# DDR3.net
KiCad netlist of a schematic drawn in Altium Designer
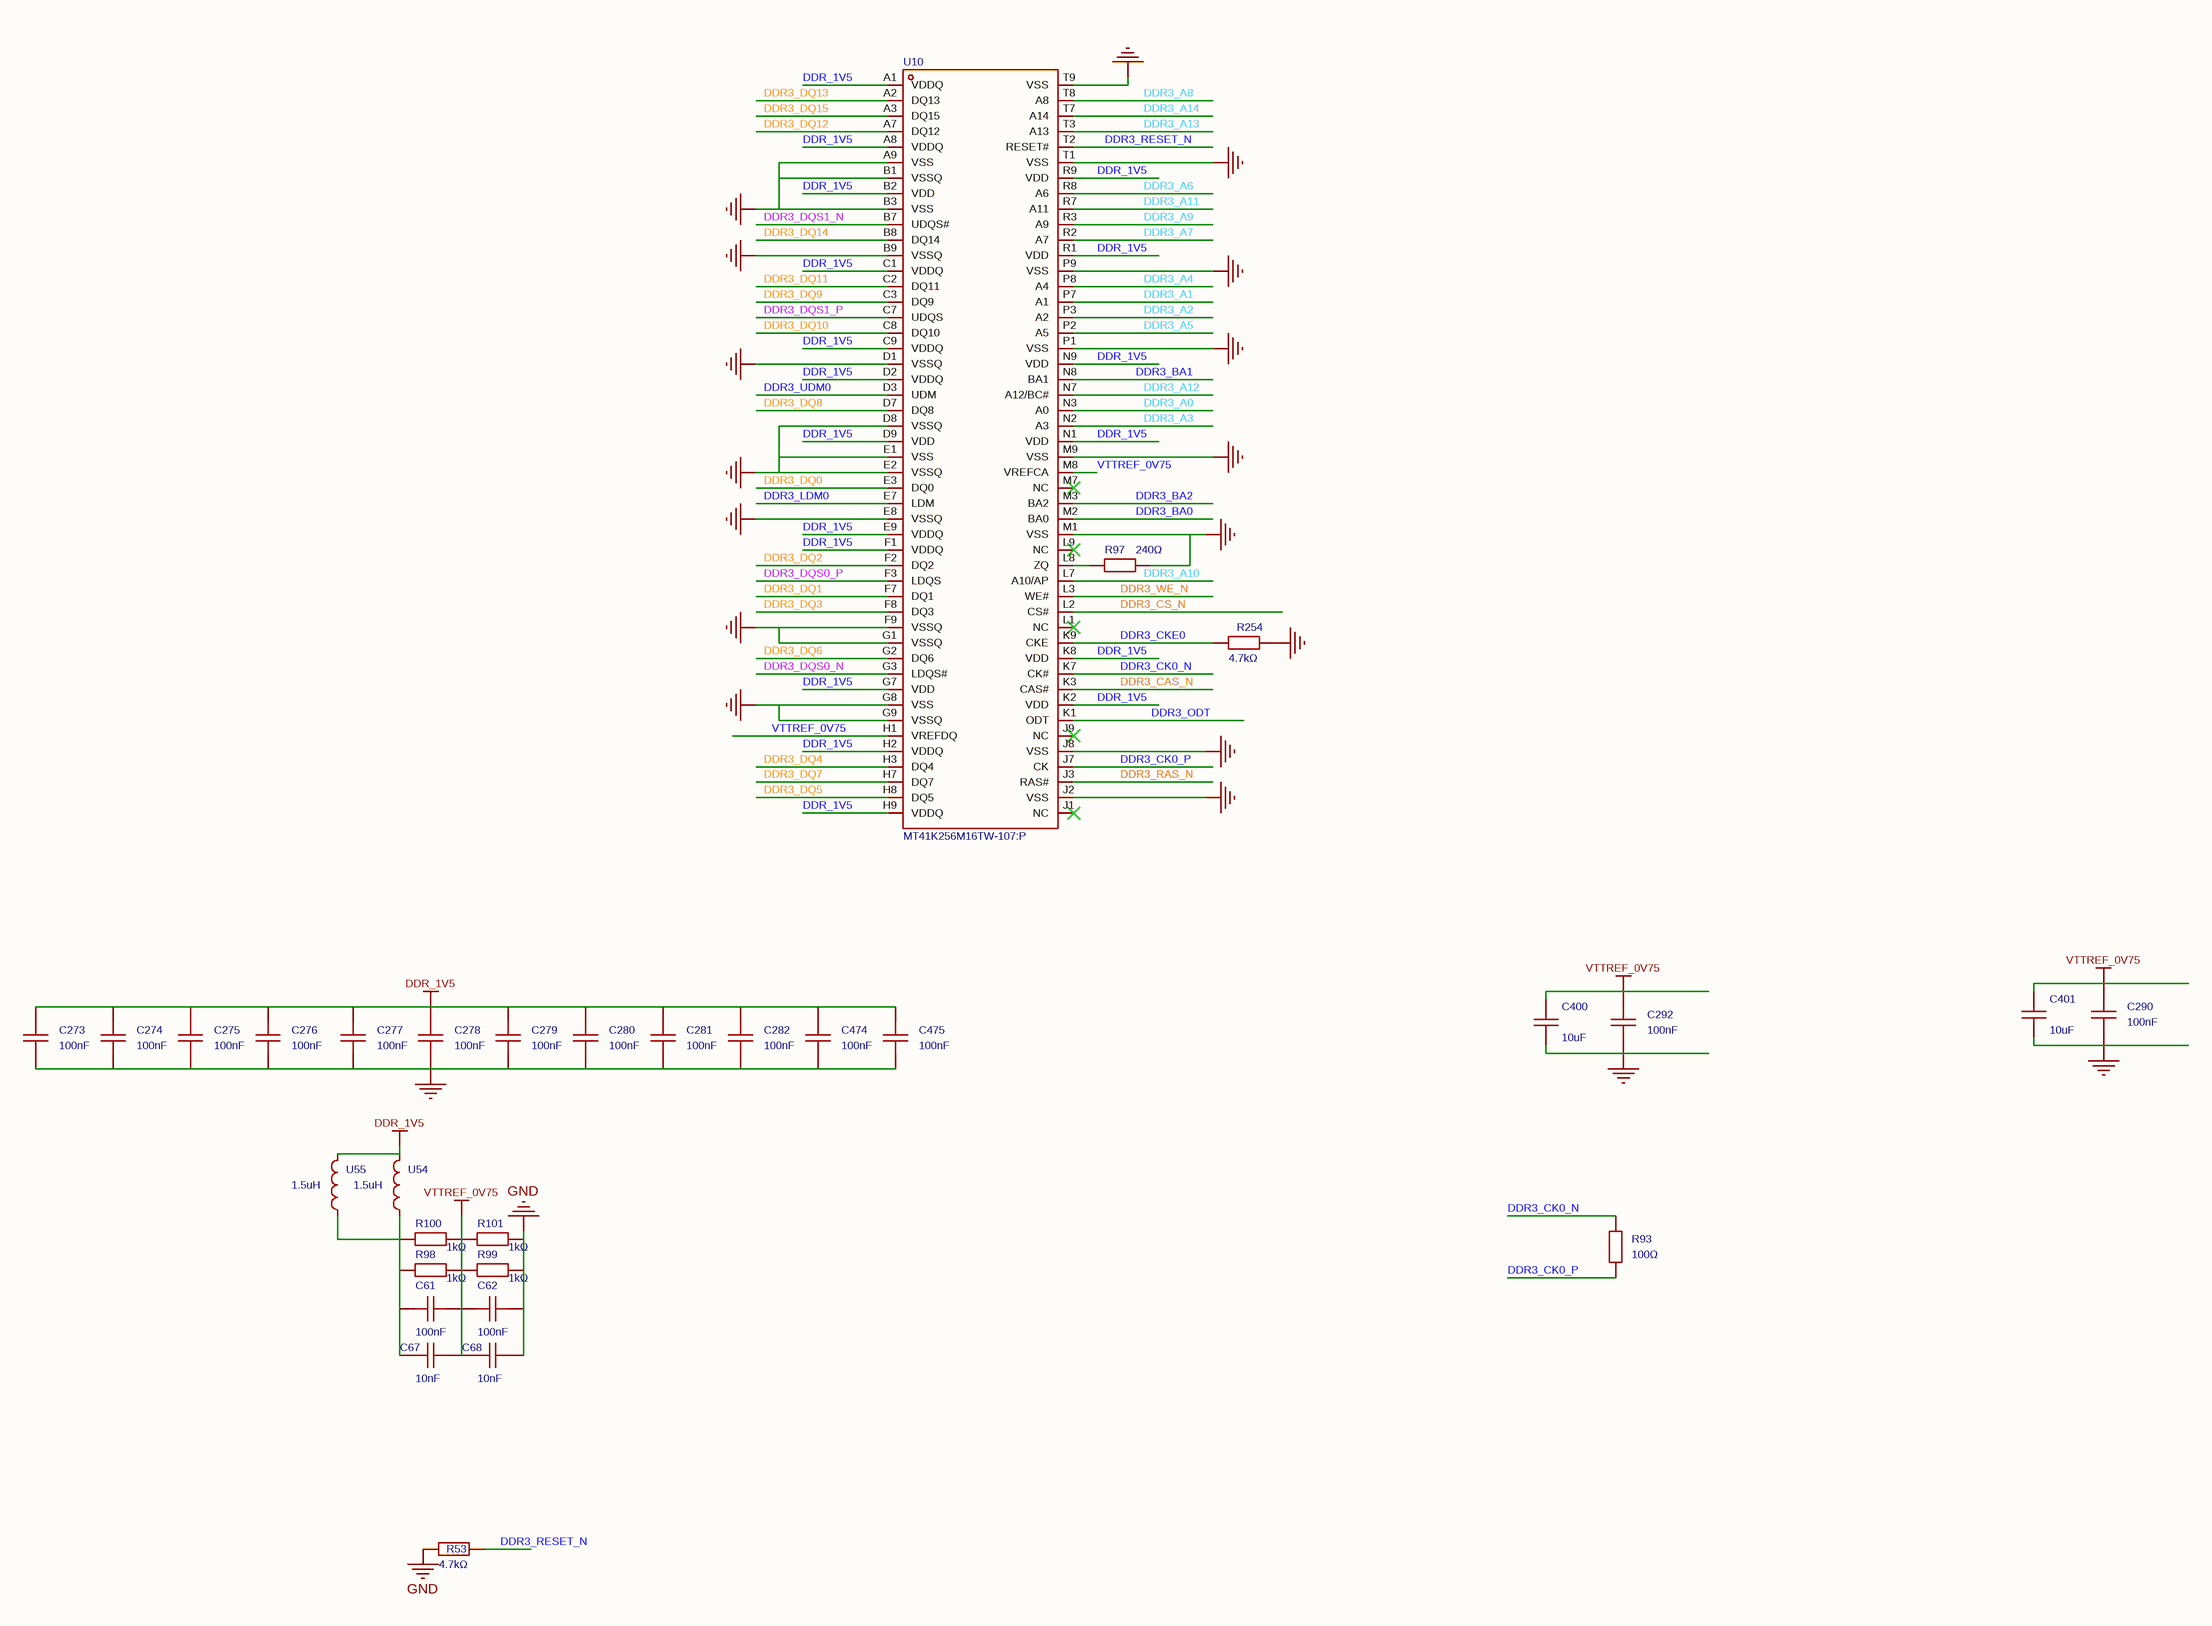
[diagram p0: DDR3.schdoc]

(export (version "E")
  (design (tool "Eeschema 10.0.6"))
  (components
    (comp (ref "C61")
      (value "100nF")
      (footprint "C0402")
      (description "容值:100nF;精度:±10%;额定电压:50V;材质(温度系数):X7R;")
      (fields (field (name "MANUFACTURER") "FH(风华)") (field (name "MANUFACTURERPART") "0402B104K500NT"))
      (libsource (lib "altium-import") (part "root_0_0402B104K500NT_"))
    )
    (comp (ref "C62")
      (value "100nF")
      (footprint "C0402")
      (description "容值:100nF;精度:±10%;额定电压:50V;材质(温度系数):X7R;")
      (fields (field (name "MANUFACTURER") "FH(风华)") (field (name "MANUFACTURERPART") "0402B104K500NT"))
      (libsource (lib "altium-import") (part "root_0_0402B104K500NT_"))
    )
    (comp (ref "C67")
      (value "10nF")
      (footprint "C0402")
      (description "容值:10nF;精度:±10%;额定电压:50V;材质(温度系数):X7R;")
      (fields (field (name "MANUFACTURER") "YAGEO(国巨)") (field (name "MANUFACTURERPART") "CC0402KRX7R9BB103"))
      (libsource (lib "altium-import") (part "root_0_CC0402KRX7R9BB103_"))
    )
    (comp (ref "C68")
      (value "10nF")
      (footprint "C0402")
      (description "容值:10nF;精度:±10%;额定电压:50V;材质(温度系数):X7R;")
      (fields (field (name "MANUFACTURER") "YAGEO(国巨)") (field (name "MANUFACTURERPART") "CC0402KRX7R9BB103"))
      (libsource (lib "altium-import") (part "root_0_CC0402KRX7R9BB103_"))
    )
    (comp (ref "C273")
      (value "100nF")
      (footprint "C0402")
      (description "容值:100nF;精度:±10%;额定电压:50V;材质(温度系数):X7R;")
      (fields (field (name "MANUFACTURER") "SAMSUNG(三星)") (field (name "MANUFACTURERPART") "CL05B104KB54PNC"))
      (libsource (lib "altium-import") (part "root_1_CL05B104KB54PNC_"))
    )
    (comp (ref "C274")
      (value "100nF")
      (footprint "C0402")
      (description "容值:100nF;精度:±10%;额定电压:50V;材质(温度系数):X7R;")
      (fields (field (name "MANUFACTURER") "SAMSUNG(三星)") (field (name "MANUFACTURERPART") "CL05B104KB54PNC"))
      (libsource (lib "altium-import") (part "root_1_CL05B104KB54PNC_"))
    )
    (comp (ref "C275")
      (value "100nF")
      (footprint "C0402")
      (description "容值:100nF;精度:±10%;额定电压:50V;材质(温度系数):X7R;")
      (fields (field (name "MANUFACTURER") "SAMSUNG(三星)") (field (name "MANUFACTURERPART") "CL05B104KB54PNC"))
      (libsource (lib "altium-import") (part "root_1_CL05B104KB54PNC_"))
    )
    (comp (ref "C276")
      (value "100nF")
      (footprint "C0402")
      (description "容值:100nF;精度:±10%;额定电压:50V;材质(温度系数):X7R;")
      (fields (field (name "MANUFACTURER") "SAMSUNG(三星)") (field (name "MANUFACTURERPART") "CL05B104KB54PNC"))
      (libsource (lib "altium-import") (part "root_1_CL05B104KB54PNC_"))
    )
    (comp (ref "C277")
      (value "100nF")
      (footprint "C0402")
      (description "容值:100nF;精度:±10%;额定电压:50V;材质(温度系数):X7R;")
      (fields (field (name "MANUFACTURER") "SAMSUNG(三星)") (field (name "MANUFACTURERPART") "CL05B104KB54PNC"))
      (libsource (lib "altium-import") (part "root_1_CL05B104KB54PNC_"))
    )
    (comp (ref "C278")
      (value "100nF")
      (footprint "C0402")
      (description "容值:100nF;精度:±10%;额定电压:50V;材质(温度系数):X7R;")
      (fields (field (name "MANUFACTURER") "SAMSUNG(三星)") (field (name "MANUFACTURERPART") "CL05B104KB54PNC"))
      (libsource (lib "altium-import") (part "root_1_CL05B104KB54PNC_"))
    )
    (comp (ref "C279")
      (value "100nF")
      (footprint "C0402")
      (description "容值:100nF;精度:±10%;额定电压:50V;材质(温度系数):X7R;")
      (fields (field (name "MANUFACTURER") "SAMSUNG(三星)") (field (name "MANUFACTURERPART") "CL05B104KB54PNC"))
      (libsource (lib "altium-import") (part "root_1_CL05B104KB54PNC_"))
    )
    (comp (ref "C280")
      (value "100nF")
      (footprint "C0402")
      (description "容值:100nF;精度:±10%;额定电压:50V;材质(温度系数):X7R;")
      (fields (field (name "MANUFACTURER") "SAMSUNG(三星)") (field (name "MANUFACTURERPART") "CL05B104KB54PNC"))
      (libsource (lib "altium-import") (part "root_1_CL05B104KB54PNC_"))
    )
    (comp (ref "C281")
      (value "100nF")
      (footprint "C0402")
      (description "容值:100nF;精度:±10%;额定电压:50V;材质(温度系数):X7R;")
      (fields (field (name "MANUFACTURER") "SAMSUNG(三星)") (field (name "MANUFACTURERPART") "CL05B104KB54PNC"))
      (libsource (lib "altium-import") (part "root_1_CL05B104KB54PNC_"))
    )
    (comp (ref "C282")
      (value "100nF")
      (footprint "C0402")
      (description "容值:100nF;精度:±10%;额定电压:50V;材质(温度系数):X7R;")
      (fields (field (name "MANUFACTURER") "SAMSUNG(三星)") (field (name "MANUFACTURERPART") "CL05B104KB54PNC"))
      (libsource (lib "altium-import") (part "root_1_CL05B104KB54PNC_"))
    )
    (comp (ref "C290")
      (value "100nF")
      (footprint "C0402")
      (description "容值:100nF;精度:±10%;额定电压:50V;材质(温度系数):X7R;")
      (fields (field (name "MANUFACTURER") "SAMSUNG(三星)") (field (name "MANUFACTURERPART") "CL05B104KB54PNC"))
      (libsource (lib "altium-import") (part "root_1_CL05B104KB54PNC_"))
    )
    (comp (ref "C292")
      (value "100nF")
      (footprint "C0402")
      (description "容值:100nF;精度:±10%;额定电压:50V;材质(温度系数):X7R;")
      (fields (field (name "MANUFACTURER") "SAMSUNG(三星)") (field (name "MANUFACTURERPART") "CL05B104KB54PNC"))
      (libsource (lib "altium-import") (part "root_1_CL05B104KB54PNC_"))
    )
    (comp (ref "C400")
      (value "10uF")
      (footprint "C0402")
      (description "容值:10uF;精度:±20%;额定电压:6.3V;材质(温度系数):X5R;")
      (fields
        (field (name "MANUFACTURER PART") "CL05A106MQ5NUNC")
        (field (name "MANUFACTURER") "SAMSUNG(三星)")
      )
      (libsource (lib "altium-import") (part "root_1_CL05A106MQ5NUNC_"))
    )
    (comp (ref "C401")
      (value "10uF")
      (footprint "C0402")
      (description "容值:10uF;精度:±20%;额定电压:6.3V;材质(温度系数):X5R;")
      (fields
        (field (name "MANUFACTURER PART") "CL05A106MQ5NUNC")
        (field (name "MANUFACTURER") "SAMSUNG(三星)")
      )
      (libsource (lib "altium-import") (part "root_1_CL05A106MQ5NUNC_"))
    )
    (comp (ref "C474")
      (value "100nF")
      (footprint "C0402")
      (description "容值:100nF;精度:±10%;额定电压:50V;材质(温度系数):X7R;")
      (fields (field (name "MANUFACTURER") "SAMSUNG(三星)") (field (name "MANUFACTURERPART") "CL05B104KB54PNC"))
      (libsource (lib "altium-import") (part "root_1_CL05B104KB54PNC_"))
    )
    (comp (ref "C475")
      (value "100nF")
      (footprint "C0402")
      (description "容值:100nF;精度:±10%;额定电压:50V;材质(温度系数):X7R;")
      (fields (field (name "MANUFACTURER") "SAMSUNG(三星)") (field (name "MANUFACTURERPART") "CL05B104KB54PNC"))
      (libsource (lib "altium-import") (part "root_1_CL05B104KB54PNC_"))
    )
    (comp (ref "R53")
      (value "4.7kΩ")
      (footprint "R0402")
      (description "电阻类型:厚膜电阻;阻值:4.7kΩ;精度:±1%;功率:62.5mW;最大工作电压:50V;温度系数:±100ppm/℃;")
      (fields
        (field (name "MANUFACTURER") "UNI-ROYAL(厚声)")
        (field (name "MANUFACTURERPART") "0402WGF4701TCE")
      )
      (libsource (lib "altium-import") (part "root_0_0402WGF4701TCE_"))
    )
    (comp (ref "R93")
      (value "100Ω")
      (footprint "R0603")
      (description "电阻类型:薄膜电阻;阻值:100Ω;精度:±0.1%;功率:100mW;最大工作电压:75V;温度系数:±25ppm/℃;")
      (fields (field (name "MANUFACTURER") "YAGEO(国巨)") (field (name "MANUFACTURERPART") "RT0603BRD07100RL"))
      (libsource (lib "altium-import") (part "root_1_RT0603BRD07100RL_"))
    )
    (comp (ref "R97")
      (value "240Ω")
      (footprint "R0402")
      (description "电阻类型:厚膜电阻;阻值:240Ω;精度:±1%;功率:62.5mW;最大工作电压:50V;温度系数:±100ppm/℃;")
      (fields
        (field (name "MANUFACTURER") "UNI-ROYAL(厚声)")
        (field (name "MANUFACTURER PART") "0402WGF2400TCE")
      )
      (libsource (lib "altium-import") (part "root_0_0402WGF2400TCE_"))
    )
    (comp (ref "R98")
      (value "1kΩ")
      (footprint "R0603")
      (description "电阻类型:薄膜电阻;阻值:1kΩ;精度:±0.1%;功率:100mW;最大工作电压:75V;温度系数:±25ppm/℃;")
      (fields (field (name "MANUFACTURER") "YAGEO(国巨)") (field (name "MANUFACTURERPART") "RT0603BRD071KL"))
      (libsource (lib "altium-import") (part "root_0_RT0603BRD071KL_"))
    )
    (comp (ref "R99")
      (value "1kΩ")
      (footprint "R0603")
      (description "电阻类型:薄膜电阻;阻值:1kΩ;精度:±0.1%;功率:100mW;最大工作电压:75V;温度系数:±25ppm/℃;")
      (fields (field (name "MANUFACTURER") "YAGEO(国巨)") (field (name "MANUFACTURERPART") "RT0603BRD071KL"))
      (libsource (lib "altium-import") (part "root_0_RT0603BRD071KL_"))
    )
    (comp (ref "R100")
      (value "1kΩ")
      (footprint "R0603")
      (description "电阻类型:薄膜电阻;阻值:1kΩ;精度:±0.1%;功率:100mW;最大工作电压:75V;温度系数:±25ppm/℃;")
      (fields (field (name "MANUFACTURER") "YAGEO(国巨)") (field (name "MANUFACTURERPART") "RT0603BRD071KL"))
      (libsource (lib "altium-import") (part "root_0_RT0603BRD071KL_"))
    )
    (comp (ref "R101")
      (value "1kΩ")
      (footprint "R0603")
      (description "电阻类型:薄膜电阻;阻值:1kΩ;精度:±0.1%;功率:100mW;最大工作电压:75V;温度系数:±25ppm/℃;")
      (fields (field (name "MANUFACTURER") "YAGEO(国巨)") (field (name "MANUFACTURERPART") "RT0603BRD071KL"))
      (libsource (lib "altium-import") (part "root_0_RT0603BRD071KL_"))
    )
    (comp (ref "R254")
      (value "4.7kΩ")
      (footprint "R0402")
      (description "电阻类型:厚膜电阻;阻值:4.7kΩ;精度:±1%;功率:62.5mW;最大工作电压:50V;温度系数:±100ppm/℃;")
      (fields
        (field (name "MANUFACTURER") "UNI-ROYAL(厚声)")
        (field (name "MANUFACTURERPART") "0402WGF4701TCE")
      )
      (libsource (lib "altium-import") (part "root_0_0402WGF4701TCE_"))
    )
    (comp (ref "U10")
      (value "MT41K256M16TW-107:P")
      (footprint "FBGA-96_L14.0-W8.0-R16-C6-P0.80-TL")
      (description "商业级")
      (fields (field (name "MANUFACTURER") "micron(镁光)"))
      (libsource (lib "altium-import") (part "root_0_MT41K256M16TW-107{colon}P_"))
    )
    (comp (ref "U54")
      (value "1.5uH")
      (footprint "L0603")
      (description "电感值:1.5uH;精度:±20%;额定电流:-;饱和电流(Isat):-;类型:-;")
      (fields (field (name "MANUFACTURER") "FH(风华)") (field (name "MANUFACTURERPART") "CMH160808B1R5MT"))
      (libsource (lib "altium-import") (part "root_1_CMH160808B1R5MT_"))
    )
    (comp (ref "U55")
      (value "1.5uH")
      (footprint "L0603")
      (description "电感值:1.5uH;精度:±20%;额定电流:-;饱和电流(Isat):-;类型:-;")
      (fields (field (name "MANUFACTURER") "FH(风华)") (field (name "MANUFACTURERPART") "CMH160808B1R5MT"))
      (libsource (lib "altium-import") (part "root_1_CMH160808B1R5MT_"))
    )
  )
  (nets
    (net (code "1") (name "/DDR3_A0") (class "Default")
      (node (ref "U10") (pin "N3") (pinfunction "A0_N3") (pintype "passive"))
    )
    (net (code "2") (name "/DDR3_A1") (class "Default")
      (node (ref "U10") (pin "P7") (pinfunction "A1_P7") (pintype "passive"))
    )
    (net (code "3") (name "/DDR3_A2") (class "Default")
      (node (ref "U10") (pin "P3") (pinfunction "A2_P3") (pintype "passive"))
    )
    (net (code "4") (name "/DDR3_A3") (class "Default")
      (node (ref "U10") (pin "N2") (pinfunction "A3_N2") (pintype "passive"))
    )
    (net (code "5") (name "/DDR3_A4") (class "Default")
      (node (ref "U10") (pin "P8") (pinfunction "A4_P8") (pintype "passive"))
    )
    (net (code "6") (name "/DDR3_A5") (class "Default")
      (node (ref "U10") (pin "P2") (pinfunction "A5_P2") (pintype "passive"))
    )
    (net (code "7") (name "/DDR3_A6") (class "Default")
      (node (ref "U10") (pin "R8") (pinfunction "A6_R8") (pintype "passive"))
    )
    (net (code "8") (name "/DDR3_A7") (class "Default")
      (node (ref "U10") (pin "R2") (pinfunction "A7_R2") (pintype "passive"))
    )
    (net (code "9") (name "/DDR3_A8") (class "Default")
      (node (ref "U10") (pin "T8") (pinfunction "A8_T8") (pintype "passive"))
    )
    (net (code "10") (name "/DDR3_A9") (class "Default")
      (node (ref "U10") (pin "R3") (pinfunction "A9_R3") (pintype "passive"))
    )
    (net (code "11") (name "/DDR3_A10") (class "Default")
      (node (ref "U10") (pin "L7") (pinfunction "A10/AP_L7") (pintype "passive"))
    )
    (net (code "12") (name "/DDR3_A11") (class "Default")
      (node (ref "U10") (pin "R7") (pinfunction "A11_R7") (pintype "passive"))
    )
    (net (code "13") (name "/DDR3_A12") (class "Default")
      (node (ref "U10") (pin "N7") (pinfunction "A12/BC#_N7") (pintype "passive"))
    )
    (net (code "14") (name "/DDR3_A13") (class "Default")
      (node (ref "U10") (pin "T3") (pinfunction "A13_T3") (pintype "passive"))
    )
    (net (code "15") (name "/DDR3_A14") (class "Default")
      (node (ref "U10") (pin "T7") (pinfunction "A14_T7") (pintype "passive"))
    )
    (net (code "16") (name "/DDR3_BA0") (class "Default")
      (node (ref "U10") (pin "M2") (pinfunction "BA0_M2") (pintype "passive"))
    )
    (net (code "17") (name "/DDR3_BA1") (class "Default")
      (node (ref "U10") (pin "N8") (pinfunction "BA1_N8") (pintype "passive"))
    )
    (net (code "18") (name "/DDR3_BA2") (class "Default")
      (node (ref "U10") (pin "M3") (pinfunction "BA2_M3") (pintype "passive"))
    )
    (net (code "19") (name "/DDR3_CAS_N") (class "Default")
      (node (ref "U10") (pin "K3") (pinfunction "CAS#_K3") (pintype "passive"))
    )
    (net (code "20") (name "/DDR3_CK0_N") (class "Default")
      (node (ref "R93") (pin "2") (pinfunction "2_2") (pintype "passive"))
      (node (ref "U10") (pin "K7") (pinfunction "CK#_K7") (pintype "passive"))
    )
    (net (code "21") (name "/DDR3_CK0_P") (class "Default")
      (node (ref "R93") (pin "1") (pinfunction "1_1") (pintype "passive"))
      (node (ref "U10") (pin "J7") (pinfunction "CK_J7") (pintype "passive"))
    )
    (net (code "22") (name "/DDR3_CKE0") (class "Default")
      (node (ref "R254") (pin "1") (pinfunction "1_1") (pintype "passive"))
      (node (ref "U10") (pin "K9") (pinfunction "CKE_K9") (pintype "passive"))
    )
    (net (code "23") (name "/DDR3_CS_N") (class "Default")
      (node (ref "U10") (pin "L2") (pinfunction "CS#_L2") (pintype "passive"))
    )
    (net (code "24") (name "/DDR3_DQ0") (class "Default")
      (node (ref "U10") (pin "E3") (pinfunction "DQ0_E3") (pintype "passive"))
    )
    (net (code "25") (name "/DDR3_DQ1") (class "Default")
      (node (ref "U10") (pin "F7") (pinfunction "DQ1_F7") (pintype "passive"))
    )
    (net (code "26") (name "/DDR3_DQ2") (class "Default")
      (node (ref "U10") (pin "F2") (pinfunction "DQ2_F2") (pintype "passive"))
    )
    (net (code "27") (name "/DDR3_DQ3") (class "Default")
      (node (ref "U10") (pin "F8") (pinfunction "DQ3_F8") (pintype "passive"))
    )
    (net (code "28") (name "/DDR3_DQ4") (class "Default")
      (node (ref "U10") (pin "H3") (pinfunction "DQ4_H3") (pintype "passive"))
    )
    (net (code "29") (name "/DDR3_DQ5") (class "Default")
      (node (ref "U10") (pin "H8") (pinfunction "DQ5_H8") (pintype "passive"))
    )
    (net (code "30") (name "/DDR3_DQ6") (class "Default")
      (node (ref "U10") (pin "G2") (pinfunction "DQ6_G2") (pintype "passive"))
    )
    (net (code "31") (name "/DDR3_DQ7") (class "Default")
      (node (ref "U10") (pin "H7") (pinfunction "DQ7_H7") (pintype "passive"))
    )
    (net (code "32") (name "/DDR3_DQ8") (class "Default")
      (node (ref "U10") (pin "D7") (pinfunction "DQ8_D7") (pintype "passive"))
    )
    (net (code "33") (name "/DDR3_DQ9") (class "Default")
      (node (ref "U10") (pin "C3") (pinfunction "DQ9_C3") (pintype "passive"))
    )
    (net (code "34") (name "/DDR3_DQ10") (class "Default")
      (node (ref "U10") (pin "C8") (pinfunction "DQ10_C8") (pintype "passive"))
    )
    (net (code "35") (name "/DDR3_DQ11") (class "Default")
      (node (ref "U10") (pin "C2") (pinfunction "DQ11_C2") (pintype "passive"))
    )
    (net (code "36") (name "/DDR3_DQ12") (class "Default")
      (node (ref "U10") (pin "A7") (pinfunction "DQ12_A7") (pintype "passive"))
    )
    (net (code "37") (name "/DDR3_DQ13") (class "Default")
      (node (ref "U10") (pin "A2") (pinfunction "DQ13_A2") (pintype "passive"))
    )
    (net (code "38") (name "/DDR3_DQ14") (class "Default")
      (node (ref "U10") (pin "B8") (pinfunction "DQ14_B8") (pintype "passive"))
    )
    (net (code "39") (name "/DDR3_DQ15") (class "Default")
      (node (ref "U10") (pin "A3") (pinfunction "DQ15_A3") (pintype "passive"))
    )
    (net (code "40") (name "/DDR3_DQS0_N") (class "Default")
      (node (ref "U10") (pin "G3") (pinfunction "LDQS#_G3") (pintype "passive"))
    )
    (net (code "41") (name "/DDR3_DQS0_P") (class "Default")
      (node (ref "U10") (pin "F3") (pinfunction "LDQS_F3") (pintype "passive"))
    )
    (net (code "42") (name "/DDR3_DQS1_N") (class "Default")
      (node (ref "U10") (pin "B7") (pinfunction "UDQS#_B7") (pintype "passive"))
    )
    (net (code "43") (name "/DDR3_DQS1_P") (class "Default")
      (node (ref "U10") (pin "C7") (pinfunction "UDQS_C7") (pintype "passive"))
    )
    (net (code "44") (name "/DDR3_LDM0") (class "Default")
      (node (ref "U10") (pin "E7") (pinfunction "LDM_E7") (pintype "passive"))
    )
    (net (code "45") (name "/DDR3_ODT") (class "Default")
      (node (ref "U10") (pin "K1") (pinfunction "ODT_K1") (pintype "passive"))
    )
    (net (code "46") (name "/DDR3_RAS_N") (class "Default")
      (node (ref "U10") (pin "J3") (pinfunction "RAS#_J3") (pintype "passive"))
    )
    (net (code "47") (name "/DDR3_RESET_N") (class "Default")
      (node (ref "R53") (pin "2") (pinfunction "2_2") (pintype "passive"))
      (node (ref "U10") (pin "T2") (pinfunction "RESET#_T2") (pintype "passive"))
    )
    (net (code "48") (name "/DDR3_UDM0") (class "Default")
      (node (ref "U10") (pin "D3") (pinfunction "UDM_D3") (pintype "passive"))
    )
    (net (code "49") (name "/DDR3_WE_N") (class "Default")
      (node (ref "U10") (pin "L3") (pinfunction "WE#_L3") (pintype "passive"))
    )
    (net (code "50") (name "DDR_1V5") (class "Default")
      (node (ref "C273") (pin "2") (pinfunction "2_2") (pintype "passive"))
      (node (ref "C274") (pin "2") (pinfunction "2_2") (pintype "passive"))
      (node (ref "C275") (pin "2") (pinfunction "2_2") (pintype "passive"))
      (node (ref "C276") (pin "2") (pinfunction "2_2") (pintype "passive"))
      (node (ref "C277") (pin "2") (pinfunction "2_2") (pintype "passive"))
      (node (ref "C278") (pin "2") (pinfunction "2_2") (pintype "passive"))
      (node (ref "C279") (pin "2") (pinfunction "2_2") (pintype "passive"))
      (node (ref "C280") (pin "2") (pinfunction "2_2") (pintype "passive"))
      (node (ref "C281") (pin "2") (pinfunction "2_2") (pintype "passive"))
      (node (ref "C282") (pin "2") (pinfunction "2_2") (pintype "passive"))
      (node (ref "C474") (pin "2") (pinfunction "2_2") (pintype "passive"))
      (node (ref "C475") (pin "2") (pinfunction "2_2") (pintype "passive"))
      (node (ref "U10") (pin "A1") (pinfunction "VDDQ_A1") (pintype "passive"))
      (node (ref "U10") (pin "A8") (pinfunction "VDDQ_A8") (pintype "passive"))
      (node (ref "U10") (pin "B2") (pinfunction "VDD_B2") (pintype "passive"))
      (node (ref "U10") (pin "C1") (pinfunction "VDDQ_C1") (pintype "passive"))
      (node (ref "U10") (pin "C9") (pinfunction "VDDQ_C9") (pintype "passive"))
      (node (ref "U10") (pin "D2") (pinfunction "VDDQ_D2") (pintype "passive"))
      (node (ref "U10") (pin "D9") (pinfunction "VDD_D9") (pintype "passive"))
      (node (ref "U10") (pin "E9") (pinfunction "VDDQ_E9") (pintype "passive"))
      (node (ref "U10") (pin "F1") (pinfunction "VDDQ_F1") (pintype "passive"))
      (node (ref "U10") (pin "G7") (pinfunction "VDD_G7") (pintype "passive"))
      (node (ref "U10") (pin "H2") (pinfunction "VDDQ_H2") (pintype "passive"))
      (node (ref "U10") (pin "H9") (pinfunction "VDDQ_H9") (pintype "passive"))
      (node (ref "U10") (pin "K2") (pinfunction "VDD_K2") (pintype "passive"))
      (node (ref "U10") (pin "K8") (pinfunction "VDD_K8") (pintype "passive"))
      (node (ref "U10") (pin "N1") (pinfunction "VDD_N1") (pintype "passive"))
      (node (ref "U10") (pin "N9") (pinfunction "VDD_N9") (pintype "passive"))
      (node (ref "U10") (pin "R1") (pinfunction "VDD_R1") (pintype "passive"))
      (node (ref "U10") (pin "R9") (pinfunction "VDD_R9") (pintype "passive"))
      (node (ref "U54") (pin "2") (pinfunction "2_2") (pintype "passive"))
      (node (ref "U55") (pin "2") (pinfunction "2_2") (pintype "passive"))
    )
    (net (code "51") (name "GND") (class "Default")
      (node (ref "C273") (pin "1") (pinfunction "1_1") (pintype "passive"))
      (node (ref "C274") (pin "1") (pinfunction "1_1") (pintype "passive"))
      (node (ref "C275") (pin "1") (pinfunction "1_1") (pintype "passive"))
      (node (ref "C276") (pin "1") (pinfunction "1_1") (pintype "passive"))
      (node (ref "C277") (pin "1") (pinfunction "1_1") (pintype "passive"))
      (node (ref "C278") (pin "1") (pinfunction "1_1") (pintype "passive"))
      (node (ref "C279") (pin "1") (pinfunction "1_1") (pintype "passive"))
      (node (ref "C280") (pin "1") (pinfunction "1_1") (pintype "passive"))
      (node (ref "C281") (pin "1") (pinfunction "1_1") (pintype "passive"))
      (node (ref "C282") (pin "1") (pinfunction "1_1") (pintype "passive"))
      (node (ref "C290") (pin "1") (pinfunction "1_1") (pintype "passive"))
      (node (ref "C292") (pin "1") (pinfunction "1_1") (pintype "passive"))
      (node (ref "C400") (pin "1") (pinfunction "1_1") (pintype "passive"))
      (node (ref "C401") (pin "1") (pinfunction "1_1") (pintype "passive"))
      (node (ref "C474") (pin "1") (pinfunction "1_1") (pintype "passive"))
      (node (ref "C475") (pin "1") (pinfunction "1_1") (pintype "passive"))
      (node (ref "C62") (pin "2") (pinfunction "2_2") (pintype "passive"))
      (node (ref "C68") (pin "2") (pinfunction "2_2") (pintype "passive"))
      (node (ref "R101") (pin "2") (pinfunction "2_2") (pintype "passive"))
      (node (ref "R254") (pin "2") (pinfunction "2_2") (pintype "passive"))
      (node (ref "R53") (pin "1") (pinfunction "1_1") (pintype "passive"))
      (node (ref "R97") (pin "2") (pinfunction "2_2") (pintype "passive"))
      (node (ref "R99") (pin "2") (pinfunction "2_2") (pintype "passive"))
      (node (ref "U10") (pin "A9") (pinfunction "VSS_A9") (pintype "passive"))
      (node (ref "U10") (pin "B1") (pinfunction "VSSQ_B1") (pintype "passive"))
      (node (ref "U10") (pin "B3") (pinfunction "VSS_B3") (pintype "passive"))
      (node (ref "U10") (pin "B9") (pinfunction "VSSQ_B9") (pintype "passive"))
      (node (ref "U10") (pin "D1") (pinfunction "VSSQ_D1") (pintype "passive"))
      (node (ref "U10") (pin "D8") (pinfunction "VSSQ_D8") (pintype "passive"))
      (node (ref "U10") (pin "E1") (pinfunction "VSS_E1") (pintype "passive"))
      (node (ref "U10") (pin "E2") (pinfunction "VSSQ_E2") (pintype "passive"))
      (node (ref "U10") (pin "E8") (pinfunction "VSSQ_E8") (pintype "passive"))
      (node (ref "U10") (pin "F9") (pinfunction "VSSQ_F9") (pintype "passive"))
      (node (ref "U10") (pin "G1") (pinfunction "VSSQ_G1") (pintype "passive"))
      (node (ref "U10") (pin "G8") (pinfunction "VSS_G8") (pintype "passive"))
      (node (ref "U10") (pin "G9") (pinfunction "VSSQ_G9") (pintype "passive"))
      (node (ref "U10") (pin "J2") (pinfunction "VSS_J2") (pintype "passive"))
      (node (ref "U10") (pin "J8") (pinfunction "VSS_J8") (pintype "passive"))
      (node (ref "U10") (pin "M1") (pinfunction "VSS_M1") (pintype "passive"))
      (node (ref "U10") (pin "M9") (pinfunction "VSS_M9") (pintype "passive"))
      (node (ref "U10") (pin "P1") (pinfunction "VSS_P1") (pintype "passive"))
      (node (ref "U10") (pin "P9") (pinfunction "VSS_P9") (pintype "passive"))
      (node (ref "U10") (pin "T1") (pinfunction "VSS_T1") (pintype "passive"))
      (node (ref "U10") (pin "T9") (pinfunction "VSS_T9") (pintype "passive"))
    )
    (net (code "52") (name "Net-(C61-Pad1)") (class "Default")
      (node (ref "C61") (pin "1") (pinfunction "1_1") (pintype "passive"))
      (node (ref "C67") (pin "1") (pinfunction "1_1") (pintype "passive"))
      (node (ref "R100") (pin "1") (pinfunction "1_1") (pintype "passive"))
      (node (ref "R98") (pin "1") (pinfunction "1_1") (pintype "passive"))
      (node (ref "U54") (pin "1") (pinfunction "1_1") (pintype "passive"))
      (node (ref "U55") (pin "1") (pinfunction "1_1") (pintype "passive"))
    )
    (net (code "53") (name "Net-(U10-ZQ)") (class "Default")
      (node (ref "R97") (pin "1") (pinfunction "1_1") (pintype "passive"))
      (node (ref "U10") (pin "L8") (pinfunction "ZQ_L8") (pintype "passive"))
    )
    (net (code "54") (name "VTTREF_0V75") (class "Default")
      (node (ref "C290") (pin "2") (pinfunction "2_2") (pintype "passive"))
      (node (ref "C292") (pin "2") (pinfunction "2_2") (pintype "passive"))
      (node (ref "C400") (pin "2") (pinfunction "2_2") (pintype "passive"))
      (node (ref "C401") (pin "2") (pinfunction "2_2") (pintype "passive"))
      (node (ref "C61") (pin "2") (pinfunction "2_2") (pintype "passive"))
      (node (ref "C62") (pin "1") (pinfunction "1_1") (pintype "passive"))
      (node (ref "C67") (pin "2") (pinfunction "2_2") (pintype "passive"))
      (node (ref "C68") (pin "1") (pinfunction "1_1") (pintype "passive"))
      (node (ref "R100") (pin "2") (pinfunction "2_2") (pintype "passive"))
      (node (ref "R101") (pin "1") (pinfunction "1_1") (pintype "passive"))
      (node (ref "R98") (pin "2") (pinfunction "2_2") (pintype "passive"))
      (node (ref "R99") (pin "1") (pinfunction "1_1") (pintype "passive"))
      (node (ref "U10") (pin "H1") (pinfunction "VREFDQ_H1") (pintype "passive"))
      (node (ref "U10") (pin "M8") (pinfunction "VREFCA_M8") (pintype "passive"))
    )
    (net (code "55") (name "unconnected-(U10-NC-PadJ1)") (class "Default")
      (node (ref "U10") (pin "J1") (pinfunction "NC_J1") (pintype "passive+no_connect"))
    )
    (net (code "56") (name "unconnected-(U10-NC-PadJ9)") (class "Default")
      (node (ref "U10") (pin "J9") (pinfunction "NC_J9") (pintype "passive+no_connect"))
    )
    (net (code "57") (name "unconnected-(U10-NC-PadL1)") (class "Default")
      (node (ref "U10") (pin "L1") (pinfunction "NC_L1") (pintype "passive+no_connect"))
    )
    (net (code "58") (name "unconnected-(U10-NC-PadL9)") (class "Default")
      (node (ref "U10") (pin "L9") (pinfunction "NC_L9") (pintype "passive+no_connect"))
    )
    (net (code "59") (name "unconnected-(U10-NC-PadM7)") (class "Default")
      (node (ref "U10") (pin "M7") (pinfunction "NC_M7") (pintype "passive+no_connect"))
    )
  )
)
